# gb-001.net
KiCad netlist of a schematic drawn in EAGLE
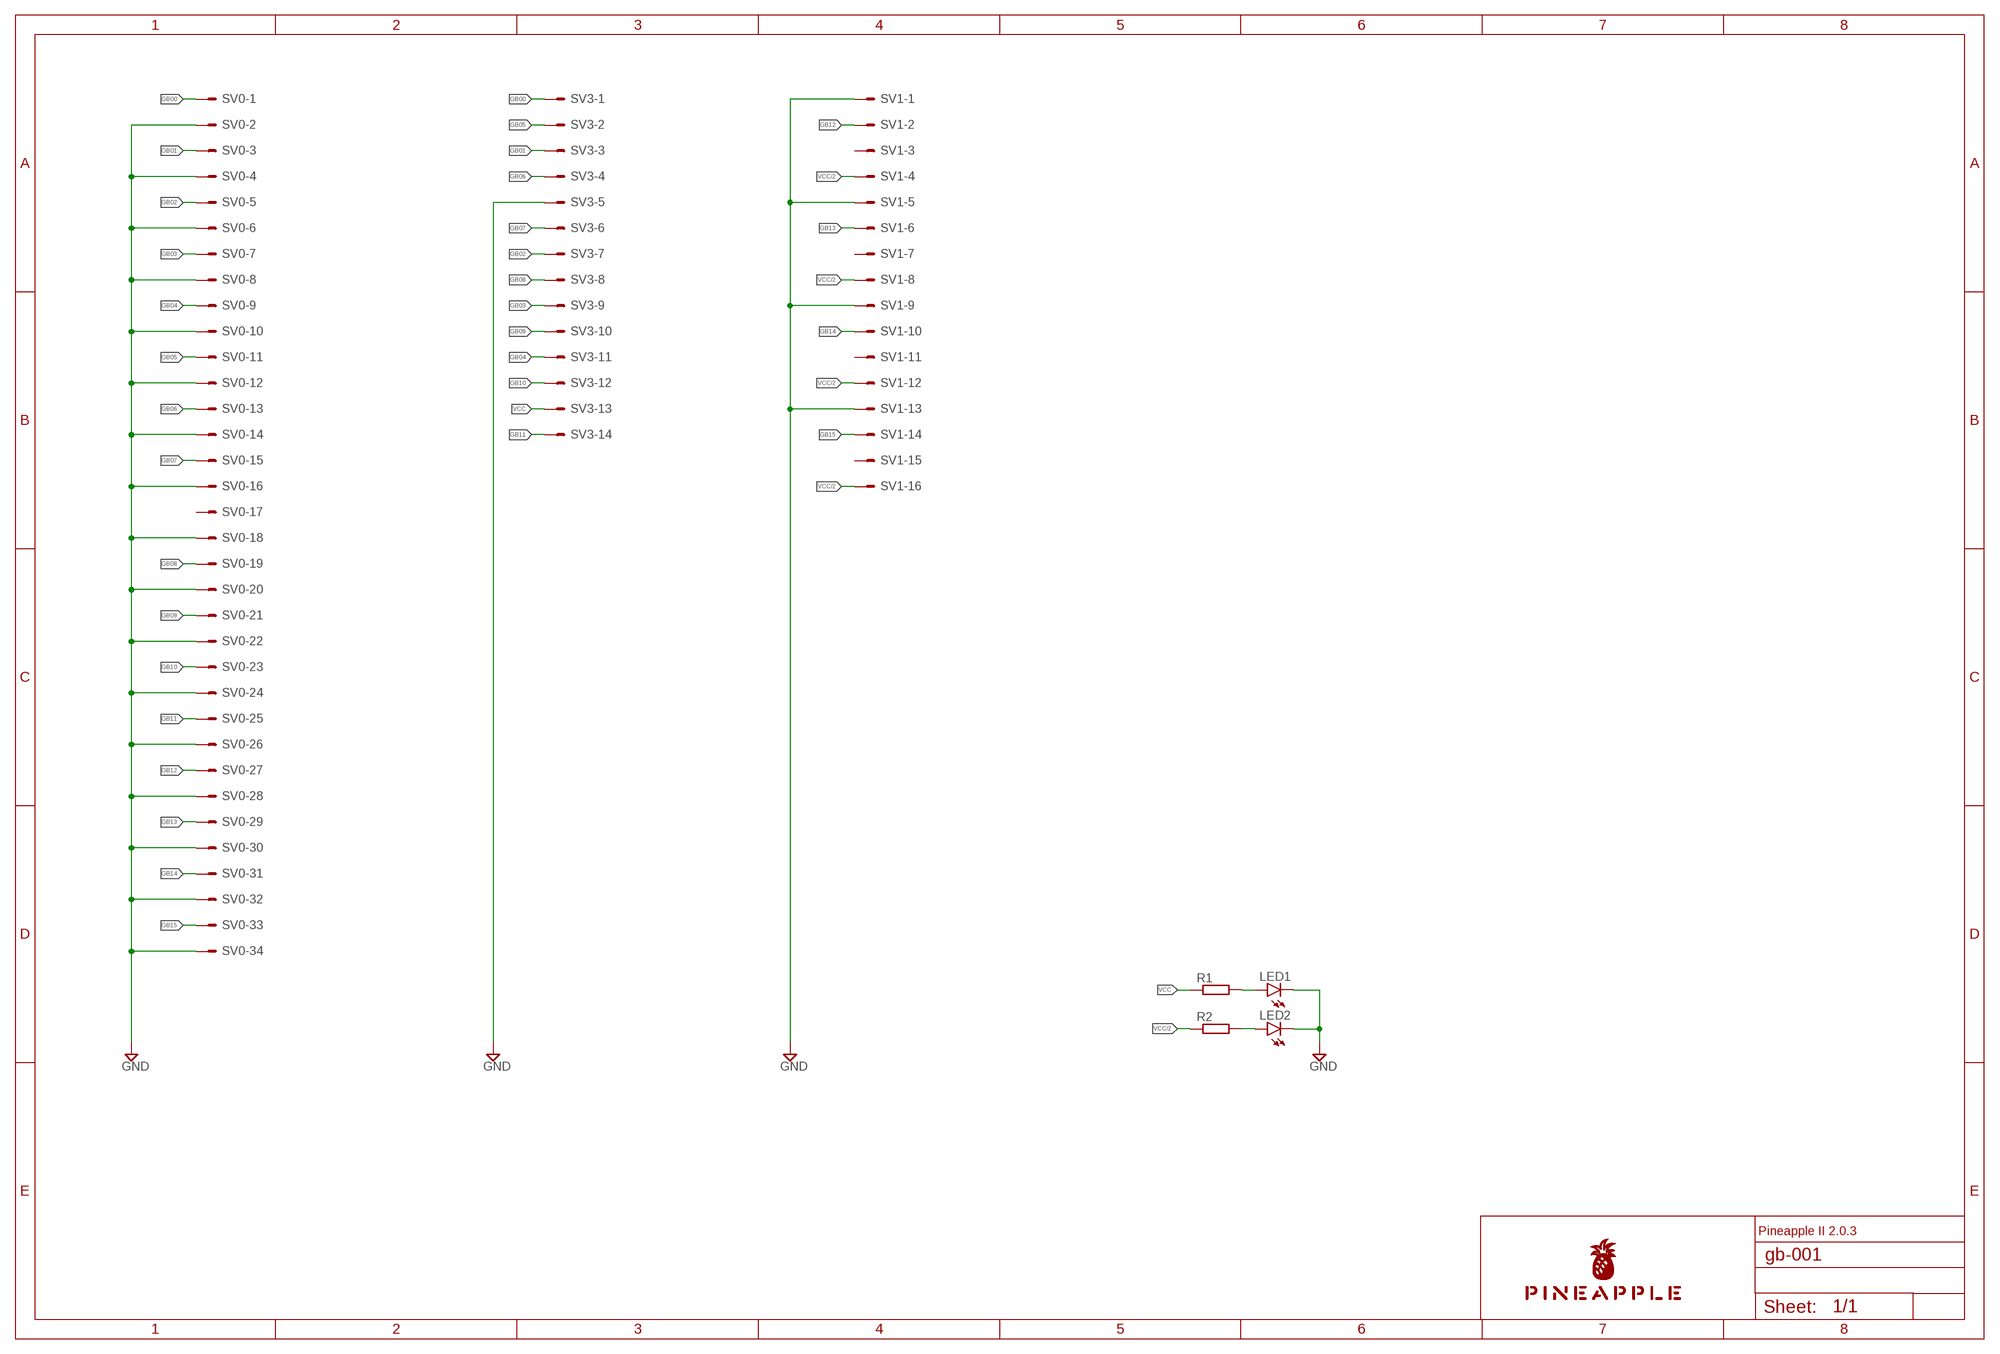
[diagram p0: schematic, sheet 1]

(export (version "E")
  (design (tool "Eeschema 10.0.6"))
  (components
    (comp (ref "LED1")
      (value "LED3MM")
      (footprint "eagle-import:LED3MM")
      (libsource (lib "eagle-import") (part "LED3MM"))
    )
    (comp (ref "LED2")
      (value "LED3MM")
      (footprint "eagle-import:LED3MM")
      (libsource (lib "eagle-import") (part "LED3MM"))
    )
    (comp (ref "R1")
      (value "R-EU_0204/5")
      (footprint "eagle-import:0204_5")
      (libsource (lib "eagle-import") (part "R-EU_0204/5"))
    )
    (comp (ref "R2")
      (value "R-EU_0204/5")
      (footprint "eagle-import:0204_5")
      (libsource (lib "eagle-import") (part "R-EU_0204/5"))
    )
    (comp (ref "SV0")
      (value "ML34LE")
      (footprint "eagle-import:ML34L")
      (libsource (lib "eagle-import") (part "ML34LE"))
    )
    (comp (ref "SV1")
      (value "ML16LE")
      (footprint "eagle-import:ML16L")
      (libsource (lib "eagle-import") (part "ML16LE"))
    )
    (comp (ref "SV3")
      (value "ML14LE")
      (footprint "eagle-import:ML14L")
      (libsource (lib "eagle-import") (part "ML14LE"))
    )
    (comp (ref "U$1")
      (value "PINEAPPLE450_SILK")
      (footprint "eagle-import:PINEAPPLE450_SILK")
      (libsource (lib "eagle-import") (part "PINEAPPLE450_SILK"))
    )
  )
  (nets
    (net (code "1") (name "GB00") (class "Default")
      (node (ref "SV0") (pin "1") (pinfunction "S_1") (pintype "passive"))
      (node (ref "SV3") (pin "1") (pinfunction "S_1") (pintype "passive"))
    )
    (net (code "2") (name "GB01") (class "Default")
      (node (ref "SV0") (pin "3") (pinfunction "S_3") (pintype "passive"))
      (node (ref "SV3") (pin "3") (pinfunction "S_3") (pintype "passive"))
    )
    (net (code "3") (name "GB02") (class "Default")
      (node (ref "SV0") (pin "5") (pinfunction "S_5") (pintype "passive"))
      (node (ref "SV3") (pin "7") (pinfunction "S_7") (pintype "passive"))
    )
    (net (code "4") (name "GB03") (class "Default")
      (node (ref "SV0") (pin "7") (pinfunction "S_7") (pintype "passive"))
      (node (ref "SV3") (pin "9") (pinfunction "S_9") (pintype "passive"))
    )
    (net (code "5") (name "GB04") (class "Default")
      (node (ref "SV0") (pin "9") (pinfunction "S_9") (pintype "passive"))
      (node (ref "SV3") (pin "11") (pinfunction "S_11") (pintype "passive"))
    )
    (net (code "6") (name "GB05") (class "Default")
      (node (ref "SV0") (pin "11") (pinfunction "S_11") (pintype "passive"))
      (node (ref "SV3") (pin "2") (pinfunction "S_2") (pintype "passive"))
    )
    (net (code "7") (name "GB06") (class "Default")
      (node (ref "SV0") (pin "13") (pinfunction "S_13") (pintype "passive"))
      (node (ref "SV3") (pin "4") (pinfunction "S_4") (pintype "passive"))
    )
    (net (code "8") (name "GB07") (class "Default")
      (node (ref "SV0") (pin "15") (pinfunction "S_15") (pintype "passive"))
      (node (ref "SV3") (pin "6") (pinfunction "S_6") (pintype "passive"))
    )
    (net (code "9") (name "GB08") (class "Default")
      (node (ref "SV0") (pin "19") (pinfunction "S_19") (pintype "passive"))
      (node (ref "SV3") (pin "8") (pinfunction "S_8") (pintype "passive"))
    )
    (net (code "10") (name "GB09") (class "Default")
      (node (ref "SV0") (pin "21") (pinfunction "S_21") (pintype "passive"))
      (node (ref "SV3") (pin "10") (pinfunction "S_10") (pintype "passive"))
    )
    (net (code "11") (name "GB10") (class "Default")
      (node (ref "SV0") (pin "23") (pinfunction "S_23") (pintype "passive"))
      (node (ref "SV3") (pin "12") (pinfunction "S_12") (pintype "passive"))
    )
    (net (code "12") (name "GB11") (class "Default")
      (node (ref "SV0") (pin "25") (pinfunction "S_25") (pintype "passive"))
      (node (ref "SV3") (pin "14") (pinfunction "S_14") (pintype "passive"))
    )
    (net (code "13") (name "GB12") (class "Default")
      (node (ref "SV0") (pin "27") (pinfunction "S_27") (pintype "passive"))
      (node (ref "SV1") (pin "2") (pinfunction "S_2") (pintype "passive"))
    )
    (net (code "14") (name "GB13") (class "Default")
      (node (ref "SV0") (pin "29") (pinfunction "S_29") (pintype "passive"))
      (node (ref "SV1") (pin "6") (pinfunction "S_6") (pintype "passive"))
    )
    (net (code "15") (name "GB14") (class "Default")
      (node (ref "SV0") (pin "31") (pinfunction "S_31") (pintype "passive"))
      (node (ref "SV1") (pin "10") (pinfunction "S_10") (pintype "passive"))
    )
    (net (code "16") (name "GB15") (class "Default")
      (node (ref "SV0") (pin "33") (pinfunction "S_33") (pintype "passive"))
      (node (ref "SV1") (pin "14") (pinfunction "S_14") (pintype "passive"))
    )
    (net (code "17") (name "GND") (class "Default")
      (node (ref "LED1") (pin "K") (pinfunction "C_K") (pintype "passive"))
      (node (ref "LED2") (pin "K") (pinfunction "C_K") (pintype "passive"))
      (node (ref "SV0") (pin "10") (pinfunction "S_10") (pintype "passive"))
      (node (ref "SV0") (pin "12") (pinfunction "S_12") (pintype "passive"))
      (node (ref "SV0") (pin "14") (pinfunction "S_14") (pintype "passive"))
      (node (ref "SV0") (pin "16") (pinfunction "S_16") (pintype "passive"))
      (node (ref "SV0") (pin "18") (pinfunction "S_18") (pintype "passive"))
      (node (ref "SV0") (pin "2") (pinfunction "S_2") (pintype "passive"))
      (node (ref "SV0") (pin "20") (pinfunction "S_20") (pintype "passive"))
      (node (ref "SV0") (pin "22") (pinfunction "S_22") (pintype "passive"))
      (node (ref "SV0") (pin "24") (pinfunction "S_24") (pintype "passive"))
      (node (ref "SV0") (pin "26") (pinfunction "S_26") (pintype "passive"))
      (node (ref "SV0") (pin "28") (pinfunction "S_28") (pintype "passive"))
      (node (ref "SV0") (pin "30") (pinfunction "S_30") (pintype "passive"))
      (node (ref "SV0") (pin "32") (pinfunction "S_32") (pintype "passive"))
      (node (ref "SV0") (pin "34") (pinfunction "S_34") (pintype "passive"))
      (node (ref "SV0") (pin "4") (pinfunction "S_4") (pintype "passive"))
      (node (ref "SV0") (pin "6") (pinfunction "S_6") (pintype "passive"))
      (node (ref "SV0") (pin "8") (pinfunction "S_8") (pintype "passive"))
      (node (ref "SV1") (pin "1") (pinfunction "S_1") (pintype "passive"))
      (node (ref "SV1") (pin "13") (pinfunction "S_13") (pintype "passive"))
      (node (ref "SV1") (pin "5") (pinfunction "S_5") (pintype "passive"))
      (node (ref "SV1") (pin "9") (pinfunction "S_9") (pintype "passive"))
      (node (ref "SV3") (pin "5") (pinfunction "S_5") (pintype "passive"))
    )
    (net (code "18") (name "Net-(LED1-PadA)") (class "Default")
      (node (ref "LED1") (pin "A") (pinfunction "A_A") (pintype "passive"))
      (node (ref "R1") (pin "2") (pinfunction "2_2") (pintype "passive"))
    )
    (net (code "19") (name "Net-(LED2-PadA)") (class "Default")
      (node (ref "LED2") (pin "A") (pinfunction "A_A") (pintype "passive"))
      (node (ref "R2") (pin "2") (pinfunction "2_2") (pintype "passive"))
    )
    (net (code "20") (name "VCC") (class "Default")
      (node (ref "R1") (pin "1") (pinfunction "1_1") (pintype "passive"))
      (node (ref "SV3") (pin "13") (pinfunction "S_13") (pintype "passive"))
    )
    (net (code "21") (name "VCC{slash}2") (class "Default")
      (node (ref "R2") (pin "1") (pinfunction "1_1") (pintype "passive"))
      (node (ref "SV1") (pin "12") (pinfunction "S_12") (pintype "passive"))
      (node (ref "SV1") (pin "16") (pinfunction "S_16") (pintype "passive"))
      (node (ref "SV1") (pin "4") (pinfunction "S_4") (pintype "passive"))
      (node (ref "SV1") (pin "8") (pinfunction "S_8") (pintype "passive"))
    )
    (net (code "22") (name "unconnected-(SV0I-S-Pad17)") (class "Default")
      (node (ref "SV0") (pin "17") (pinfunction "S_17") (pintype "passive"))
    )
    (net (code "23") (name "unconnected-(SV1C-S-Pad11)") (class "Default")
      (node (ref "SV1") (pin "11") (pinfunction "S_11") (pintype "passive"))
    )
    (net (code "24") (name "unconnected-(SV1G-S-Pad15)") (class "Default")
      (node (ref "SV1") (pin "15") (pinfunction "S_15") (pintype "passive"))
    )
    (net (code "25") (name "unconnected-(SV1J-S-Pad3)") (class "Default")
      (node (ref "SV1") (pin "3") (pinfunction "S_3") (pintype "passive"))
    )
    (net (code "26") (name "unconnected-(SV1N-S-Pad7)") (class "Default")
      (node (ref "SV1") (pin "7") (pinfunction "S_7") (pintype "passive"))
    )
  )
)
